# LTE_UART_USB_adapter.net
KiCad netlist of a schematic drawn in Altium Designer
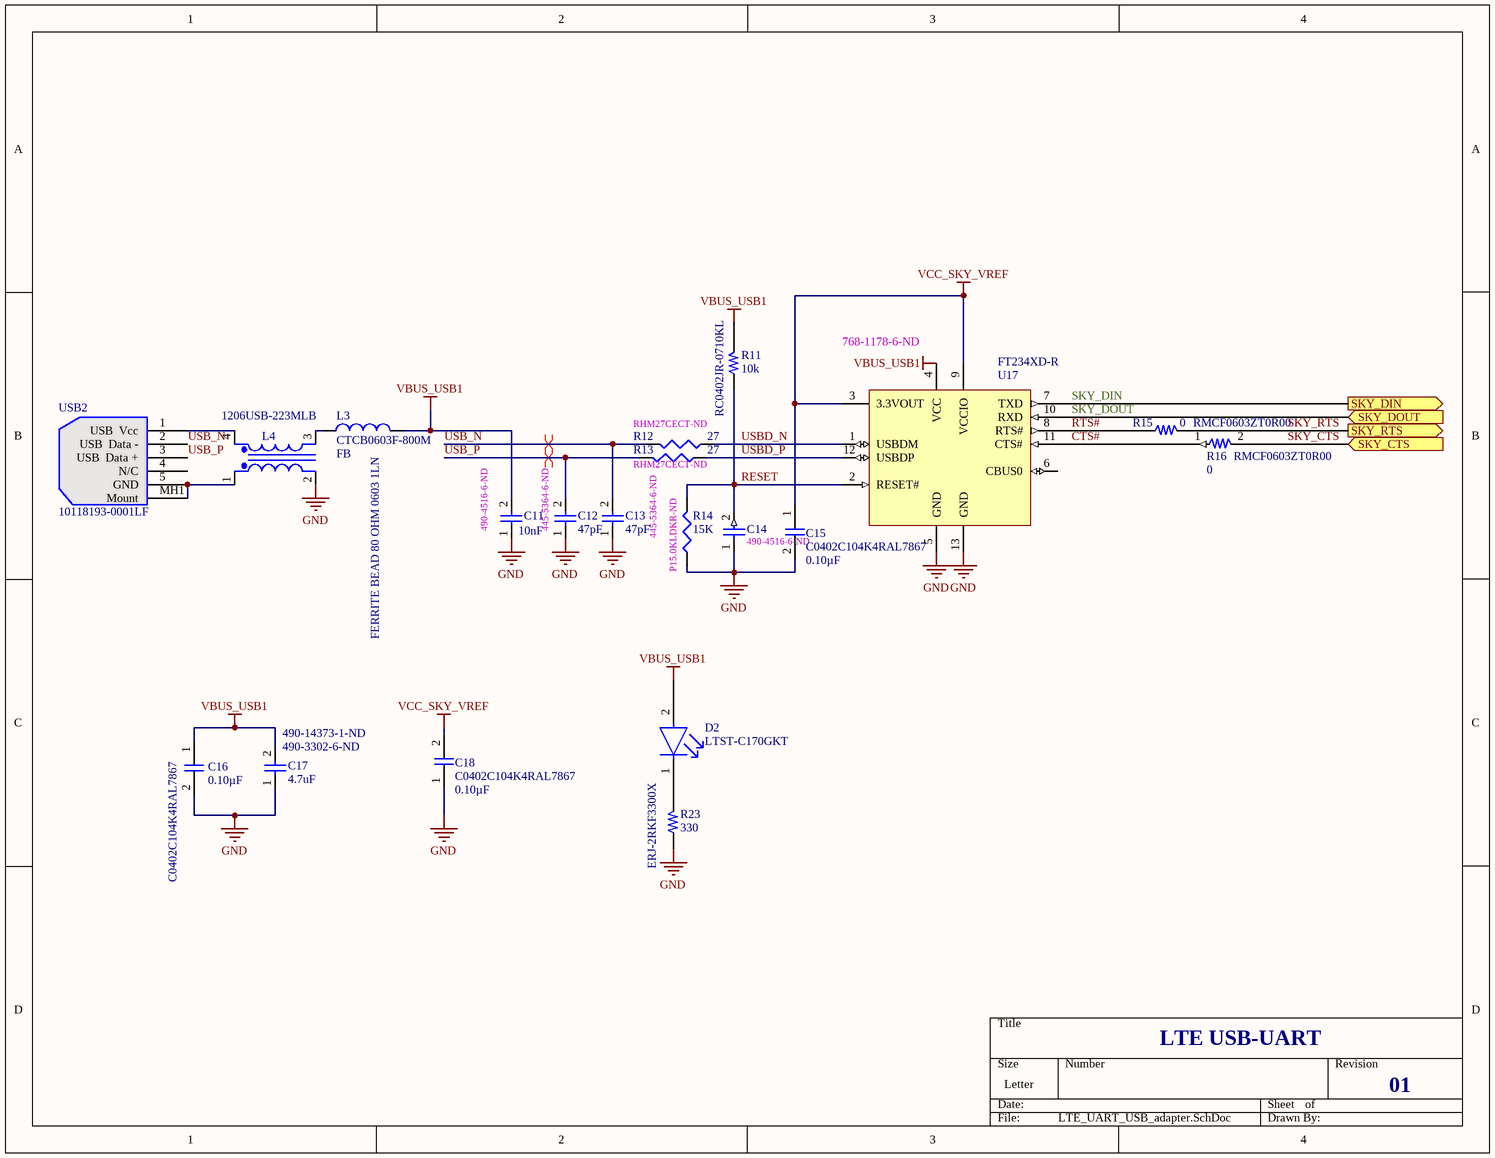
[diagram p0: LTE_UART_USB_adapter.SchDoc]

(export (version "E")
  (design (tool "Eeschema 10.0.6"))
  (components
    (comp (ref "C11")
      (value "GRM155R71H103KA88D")
      (footprint "SMD CAP 1005")
      (description "10000 pF ±10% 50V Ceramic Capacitor X7R 0402 (1005 Metric)")
      (fields
        (field (name "CAPACITANCE") "10nF")
        (field (name "DIGI-KEY PART NUMBER") "490-4516-1-ND")
        (field (name "MANUFACTURER") "Murata Electronics North America")
        (field (name "SUPPLIER PART NUMBER 1") "490-4516-6-ND")
      )
      (libsource (lib "TempProbe") (part "Cap Semi"))
    )
    (comp (ref "C12")
      (value "C1005C0G1H470G050BA")
      (footprint "SMD CAP 1005")
      (description "47 pF ±2% 50V Ceramic Capacitor C0G, NP0 0402 (1005 Metric)")
      (fields
        (field (name "CAPACITANCE") "47pF")
        (field (name "DIGI-KEY PART NUMBER") "445-5364-1-ND")
        (field (name "MANUFACTURER") "TDK Corporation")
        (field (name "SUPPLIER PART NUMBER 1") "445-5364-6-ND")
      )
      (libsource (lib "TempProbe") (part "Cap Semi"))
    )
    (comp (ref "C13")
      (value "C1005C0G1H470G050BA")
      (footprint "SMD CAP 1005")
      (description "47 pF ±2% 50V Ceramic Capacitor C0G, NP0 0402 (1005 Metric)")
      (fields
        (field (name "CAPACITANCE") "47pF")
        (field (name "DIGI-KEY PART NUMBER") "445-5364-1-ND")
        (field (name "MANUFACTURER") "TDK Corporation")
        (field (name "SUPPLIER PART NUMBER 1") "445-5364-6-ND")
      )
      (libsource (lib "TempProbe") (part "Cap Semi"))
    )
    (comp (ref "C14")
      (value "GRM155R71H103KA88D")
      (footprint "SMD CAP 1005")
      (description "10000 pF ±10% 50V Ceramic Capacitor X7R 0402 (1005 Metric)")
      (fields
        (field (name "DIGI-KEY PART NUMBER") "490-4516-1-ND")
        (field (name "MANUFACTURER") "Murata Electronics North America")
        (field (name "SUPPLIER PART NUMBER 1") "490-4516-6-ND")
      )
      (libsource (lib "TempProbe") (part "Cap Semi"))
    )
    (comp (ref "C15")
      (value "C0402C104K4RAL7867")
      (footprint "Passives:SMD CAP 1005")
      (description "0.1 µF ±10% 16V Ceramic Capacitor X7R 0402 (1005 Metric)")
      (fields
        (field (name "TOLERANCE") "±10%")
        (field (name "CAPACITANCE") "0.10µF")
        (field (name "PART_NUMBER") "1000742")
      )
      (libsource (lib "AltiumProductionDatabase") (part "C, 0.1 uF, 16V, 10%, X7R, 0402 CER"))
    )
    (comp (ref "C16")
      (value "C0402C104K4RAL7867")
      (footprint "Passives:SMD CAP 1005")
      (description "0.1 µF ±10% 16V Ceramic Capacitor X7R 0402 (1005 Metric)")
      (fields
        (field (name "TOLERANCE") "±10%")
        (field (name "CAPACITANCE") "0.10µF")
        (field (name "PART_NUMBER") "1000742")
      )
      (libsource (lib "AltiumProductionDatabase") (part "C, 0.1 uF, 16V, 10%, X7R, 0402 CER"))
    )
    (comp (ref "C17")
      (value "GRM188R61A475KAAJD")
      (footprint "CAPC1608M")
      (description "4.7 µF ±10% 10V Ceramic Capacitor X5R 0603 (1608 Metric)")
      (fields
        (field (name "CAPACITANCE") "4.7uF")
        (field (name "DIGI-KEY PART NUMBER") "490-14373-1-ND")
        (field (name "MANUFACTURER") "Murata Electronics North America")
        (field (name "SUPPLIER PART NUMBER 1") "490-3302-6-ND")
        (field (name "SUPPLIER PART NUMBER 2") "490-14373-1-ND")
      )
      (libsource (lib "TempProbe") (part "Cap Semi"))
    )
    (comp (ref "C18")
      (value "C0402C104K4RAL7867")
      (footprint "Passives:SMD CAP 1005")
      (description "0.1 µF ±10% 16V Ceramic Capacitor X7R 0402 (1005 Metric)")
      (fields
        (field (name "TOLERANCE") "±10%")
        (field (name "CAPACITANCE") "0.10µF")
        (field (name "PART_NUMBER") "1000742")
      )
      (libsource (lib "AltiumProductionDatabase") (part "C, 0.1 uF, 16V, 10%, X7R, 0402 CER"))
    )
    (comp (ref "D2")
      (value "LTST-C170GKT")
      (footprint "FP-LTST-C170GKT-MFG")
      (description "Green 569nm LED Indication - Discrete 2.1V 0805 (2012 Metric)")
      (fields (field (name "VOLTAGE") "5V") (field (name "DIGI-KEY PART NUMBER") "160-1179-1-ND"))
      (libsource (lib "Altium Content Vault") (part "8706943c75ba83719d021d2fdc84c58"))
    )
    (comp (ref "L3")
      (value "CTCB0603F-800M")
      (footprint "INDC1608M")
      (description "80 Ohms @ 100 MHz 1 Ferrite Bead 0603 (1608 Metric) 600mA 100mOhm")
      (fields
        (field (name "ALTIUM_VALUE") "FB")
        (field (name "DIGI-KEY PART NUMBER") "4161-CTCB0603F-800M-ND")
        (field (name "MANUFACTURER") "Central Technologies")
        (field (name "DESC") "FERRITE BEAD 80 OHM 0603 1LN")
        (field (name "PUBLISHER") "Altium Limited")
      )
      (libsource (lib "Miscellaneous Devices") (part "Inductor"))
    )
    (comp (ref "L4")
      (value "1206USB-223MLB")
      (footprint "1206USB-223MLB")
      (description "Common Mode Chokes / Filters")
      (fields (field (name "MANUFACTURER") "Coilcraft") (field (name "PUBLISHER") "Altium Limited"))
      (libsource (lib "Miscellaneous Devices") (part "Trans Ideal"))
    )
    (comp (ref "R11")
      (value "RC0402JR-0710KL")
      (footprint "SMD RES 1005")
      (description "10 kOhms ±5% 0.063W, 1/16W Chip Resistor 0402 (1005 Metric) Moisture Resistant Thick Film")
      (fields
        (field (name "PART_NUMBER") "RC0402JR-0710KL")
        (field (name "RESISTANCE_OHMS") "10k")
        (field (name "POWER") "0.063W, 1/16W")
        (field (name "TOLERANCE") "±1%")
      )
      (libsource (lib "AltiumProductionDatabase") (part "R, 10K, 1%, 1/16W,  0402"))
    )
    (comp (ref "R12")
      (value "27")
      (footprint "SMD RES 1005")
      (description "RES SMD 27 OHM 5% 1/16W 0402")
      (fields
        (field (name "DIGI-KEY PART NUMBER") "RHM27CECT-ND")
        (field (name "MANUFACTURER") "Rohm Semiconductor")
        (field (name "SUPPLIER PART NUMBER 1") "RHM27CECT-ND")
        (field (name "PUBLISHER") "Altium Limited")
      )
      (libsource (lib "Miscellaneous Devices") (part "Res3"))
    )
    (comp (ref "R13")
      (value "27")
      (footprint "SMD RES 1005")
      (description "RES SMD 27 OHM 5% 1/16W 0402")
      (fields
        (field (name "DIGI-KEY PART NUMBER") "RHM27CECT-ND")
        (field (name "MANUFACTURER") "Rohm Semiconductor")
        (field (name "SUPPLIER PART NUMBER 1") "RHM27CECT-ND")
        (field (name "PUBLISHER") "Altium Limited")
      )
      (libsource (lib "Miscellaneous Devices") (part "Res3"))
    )
    (comp (ref "R14")
      (value "15K")
      (footprint "SMD RES 1005")
      (description "RES SMD 15K OHM 1% 1/10W 0402")
      (fields
        (field (name "DIGI-KEY PART NUMBER") "P15.0KLCT-ND")
        (field (name "MANUFACTURER") "Panasonic Electronic Components")
        (field (name "SUPPLIER PART NUMBER 1") "P15.0KLDKR-ND")
        (field (name "PUBLISHER") "Altium Limited")
      )
      (libsource (lib "Miscellaneous Devices") (part "Res3"))
    )
    (comp (ref "R15")
      (value "RMCF0603ZT0R00")
      (footprint "RESC1608M")
      (description "0 Ohms Jumper Chip Resistor 0603 (1608 Metric) Automotive AEC-Q200 Thick Film")
      (fields
        (field (name "PART_NUMBER") "RMCF0603ZT0R00")
        (field (name "RESISTANCE") "0")
        (field (name "POWER") "0.25W, 1/4W")
        (field (name "TOLERANCE") "±1%")
      )
      (libsource (lib "AltiumProductionDatabase") (part "R, 0.1, 1%, 1/4W, 0603"))
    )
    (comp (ref "R16")
      (value "RMCF0603ZT0R00")
      (footprint "RESC1608M")
      (description "0 Ohms Jumper Chip Resistor 0603 (1608 Metric) Automotive AEC-Q200 Thick Film")
      (fields
        (field (name "PART_NUMBER") "RMCF0603ZT0R00")
        (field (name "RESISTANCE") "0")
        (field (name "POWER") "0.25W, 1/4W")
        (field (name "TOLERANCE") "±1%")
      )
      (libsource (lib "") (part "R, 0.1, 1%, 1/4W, 0603_1"))
    )
    (comp (ref "R23")
      (value "ERJ-2RKF3300X")
      (footprint "SMD RES 1005")
      (description "330 Ohms ±1% 0.1W, 1/10W Chip Resistor 0402 (1005 Metric) Automotive AEC-Q200 Thick Film")
      (fields
        (field (name "PART_NUMBER") "1001162")
        (field (name "RESISTANCE") "330")
        (field (name "POWER") "0.1W, 1/10W")
      )
      (libsource (lib "AltiumProductionDatabase") (part "R, 330, 1%, 1/10W, 0402"))
    )
    (comp (ref "U17")
      (value "FT234XD-R")
      (footprint "DFN-12_V")
      (description "IC USB SERIAL BASIC UART 12DFN")
      (fields
        (field (name "MANUFACTURER") "FTDI, Future Technology Devices International Ltd")
        (field (name "DIGI-KEY PART NUMBER") "768-1178-1-ND")
        (field (name "SUPPLIER PART NUMBER 1") "768-1178-6-ND")
      )
      (libsource (lib "Altium Content Vault") (part "CMP-0248-00027-1"))
    )
    (comp (ref "USB2")
      (value "10118193-0001LF")
      (footprint "10118193-0001LF Rev01")
      (description "USB - micro B USB 2.0 Receptacle Connector 5 Position Surface Mount, Right Angle, Horizontal")
      (fields (field (name "MANUFACTURER") "FCI") (field (name "DIGI-KEY PART NUMBER") "609-4616-1-ND"))
      (libsource (lib "USB") (part "USB mini"))
    )
  )
  (nets
    (net (code "1") (name "/CTS#") (class "Default")
      (node (ref "R16") (pin "1") (pinfunction "1_1") (pintype "output"))
      (node (ref "U17") (pin "11") (pinfunction "CTS#_11") (pintype "input"))
    )
    (net (code "2") (name "/RESET") (class "Default")
      (node (ref "C14") (pin "2") (pinfunction "2_2") (pintype "passive"))
      (node (ref "R11") (pin "1") (pinfunction "1_1") (pintype "passive"))
      (node (ref "R14") (pin "2") (pinfunction "2_2") (pintype "passive"))
      (node (ref "U17") (pin "2") (pinfunction "RESET#_2") (pintype "input"))
    )
    (net (code "3") (name "/RTS#") (class "Default")
      (node (ref "R15") (pin "1") (pinfunction "1_1") (pintype "passive"))
      (node (ref "U17") (pin "8") (pinfunction "RTS#_8") (pintype "output"))
    )
    (net (code "4") (name "/SKY_CTS") (class "Default")
      (node (ref "R16") (pin "2") (pinfunction "2_2") (pintype "passive"))
    )
    (net (code "5") (name "/SKY_DIN") (class "Default")
      (node (ref "U17") (pin "7") (pinfunction "TXD_7") (pintype "output"))
    )
    (net (code "6") (name "/SKY_DOUT") (class "Default")
      (node (ref "U17") (pin "10") (pinfunction "RXD_10") (pintype "input"))
    )
    (net (code "7") (name "/SKY_RTS") (class "Default")
      (node (ref "R15") (pin "2") (pinfunction "2_2") (pintype "passive"))
    )
    (net (code "8") (name "/USBD_N") (class "Default")
      (node (ref "R12") (pin "1") (pinfunction "1_1") (pintype "passive"))
      (node (ref "U17") (pin "1") (pinfunction "USBDM_1") (pintype "bidirectional"))
    )
    (net (code "9") (name "/USBD_P") (class "Default")
      (node (ref "R13") (pin "1") (pinfunction "1_1") (pintype "passive"))
      (node (ref "U17") (pin "12") (pinfunction "USBDP_12") (pintype "bidirectional"))
    )
    (net (code "10") (name "/USB_N") (class "Default")
      (node (ref "C13") (pin "2") (pinfunction "2_2") (pintype "passive"))
      (node (ref "R12") (pin "2") (pinfunction "2_2") (pintype "passive"))
      (node (ref "USB2") (pin "2") (pinfunction "USB__Data_-_2") (pintype "passive"))
    )
    (net (code "11") (name "/USB_P") (class "Default")
      (node (ref "C12") (pin "2") (pinfunction "2_2") (pintype "passive"))
      (node (ref "R13") (pin "2") (pinfunction "2_2") (pintype "passive"))
      (node (ref "USB2") (pin "3") (pinfunction "USB__Data_+_3") (pintype "passive"))
    )
    (net (code "12") (name "GND") (class "Default")
      (node (ref "C11") (pin "1") (pinfunction "1_1") (pintype "passive"))
      (node (ref "C12") (pin "1") (pinfunction "1_1") (pintype "passive"))
      (node (ref "C13") (pin "1") (pinfunction "1_1") (pintype "passive"))
      (node (ref "C14") (pin "1") (pinfunction "1_1") (pintype "passive"))
      (node (ref "C15") (pin "2") (pinfunction "2_2") (pintype "passive"))
      (node (ref "C16") (pin "2") (pinfunction "2_2") (pintype "passive"))
      (node (ref "C17") (pin "1") (pinfunction "1_1") (pintype "passive"))
      (node (ref "C18") (pin "1") (pinfunction "1_1") (pintype "passive"))
      (node (ref "L4") (pin "2") (pinfunction "Pri-_2") (pintype "passive"))
      (node (ref "R14") (pin "1") (pinfunction "1_1") (pintype "passive"))
      (node (ref "R23") (pin "1") (pinfunction "1_1") (pintype "passive"))
      (node (ref "U17") (pin "13") (pinfunction "GND_13") (pintype "power_in"))
      (node (ref "U17") (pin "5") (pinfunction "GND_5") (pintype "power_in"))
    )
    (net (code "13") (name "Net-(D2-C)") (class "Default")
      (node (ref "D2") (pin "1") (pinfunction "C_1") (pintype "passive"))
      (node (ref "R23") (pin "2") (pinfunction "2_2") (pintype "passive"))
    )
    (net (code "14") (name "Net-(L4-Pri+)") (class "Default")
      (node (ref "L4") (pin "1") (pinfunction "Pri+_1") (pintype "passive"))
      (node (ref "USB2") (pin "5") (pinfunction "GND_5") (pintype "passive"))
      (node (ref "USB2") (pin "MH1") (pinfunction "Mount_MH1") (pintype "passive"))
    )
    (net (code "15") (name "Net-(L4-Sec+)") (class "Default")
      (node (ref "L4") (pin "4") (pinfunction "Sec+_4") (pintype "passive"))
      (node (ref "USB2") (pin "1") (pinfunction "USB__Vcc_1") (pintype "passive"))
    )
    (net (code "16") (name "Net-(L4-Sec-)") (class "Default")
      (node (ref "L3") (pin "2") (pinfunction "2_2") (pintype "passive"))
      (node (ref "L4") (pin "3") (pinfunction "Sec-_3") (pintype "passive"))
    )
    (net (code "17") (name "VBUS_USB1") (class "Default")
      (node (ref "C11") (pin "2") (pinfunction "2_2") (pintype "passive"))
      (node (ref "C16") (pin "1") (pinfunction "1_1") (pintype "passive"))
      (node (ref "C17") (pin "2") (pinfunction "2_2") (pintype "passive"))
      (node (ref "D2") (pin "2") (pinfunction "A_2") (pintype "passive"))
      (node (ref "L3") (pin "1") (pinfunction "1_1") (pintype "passive"))
      (node (ref "R11") (pin "2") (pinfunction "2_2") (pintype "passive"))
      (node (ref "U17") (pin "4") (pinfunction "VCC_4") (pintype "power_in"))
    )
    (net (code "18") (name "VCC_SKY_VREF") (class "Default")
      (node (ref "C15") (pin "1") (pinfunction "1_1") (pintype "passive"))
      (node (ref "C18") (pin "2") (pinfunction "2_2") (pintype "passive"))
      (node (ref "U17") (pin "3") (pinfunction "3.3VOUT_3") (pintype "power_in"))
      (node (ref "U17") (pin "9") (pinfunction "VCCIO_9") (pintype "power_in"))
    )
    (net (code "19") (name "unconnected-(U17-CBUS0-Pad6)") (class "Default")
      (node (ref "U17") (pin "6") (pinfunction "CBUS0_6") (pintype "bidirectional"))
    )
    (net (code "20") (name "unconnected-(USB2-N{slash}C-Pad4)") (class "Default")
      (node (ref "USB2") (pin "4") (pinfunction "N/C_4") (pintype "passive"))
    )
  )
)
